# HotPotato.net
KiCad netlist of a schematic drawn in EAGLE
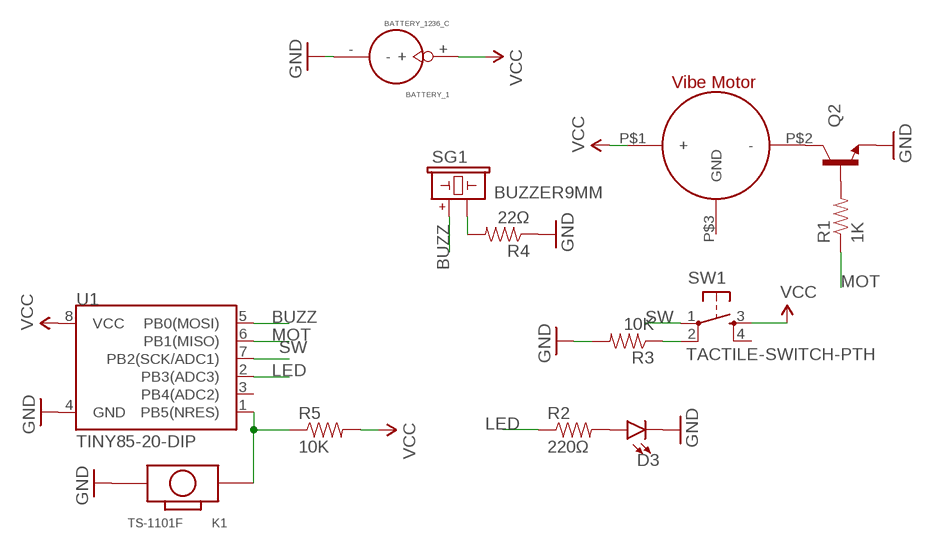
[diagram p0: schematic, sheet 1]

(export (version "E")
  (design (tool "Eeschema 10.0.6"))
  (components
    (comp (ref "BATTERY_1")
      (value "BATTERY_1236_C")
      (footprint "eagle-import:BATTERY_1236_C")
      (libsource (lib "eagle-import") (part "BATTERY_1236_C"))
    )
    (comp (ref "D3")
      (value "LED5MM-KIT")
      (footprint "eagle-import:LED_5MM-KIT")
      (libsource (lib "eagle-import") (part "LED5MM-KIT"))
    )
    (comp (ref "K1")
      (value "TS-1101F")
      (footprint "eagle-import:SW2-3.4X6.0X3.55MM-90D")
      (libsource (lib "eagle-import") (part "DIP-BUTTON-FRONT-WHITE(2P-3.4X6MM)"))
    )
    (comp (ref "M1")
      (value "SANYO_NRS-2574SMT")
      (footprint "eagle-import:SMT")
      (libsource (lib "eagle-import") (part "SANYO_NRS-2574SMT"))
    )
    (comp (ref "Q2")
      (value "TRANSISTOR_NPNBC547")
      (footprint "eagle-import:TO-92-AMMO")
      (libsource (lib "eagle-import") (part "TRANSISTOR_NPNBC547"))
    )
    (comp (ref "R1")
      (value "1K")
      (footprint "eagle-import:1206")
      (libsource (lib "eagle-import") (part "RESISTOR1206"))
    )
    (comp (ref "R2")
      (value "220Ω")
      (footprint "eagle-import:1206")
      (libsource (lib "eagle-import") (part "RESISTOR1206"))
    )
    (comp (ref "R3")
      (value "10K")
      (footprint "eagle-import:1206")
      (libsource (lib "eagle-import") (part "RESISTOR1206"))
    )
    (comp (ref "R4")
      (value "22Ω")
      (footprint "eagle-import:1206")
      (libsource (lib "eagle-import") (part "RESISTOR1206"))
    )
    (comp (ref "R5")
      (value "10K")
      (footprint "eagle-import:1206")
      (libsource (lib "eagle-import") (part "RESISTOR1206"))
    )
    (comp (ref "SG1")
      (value "BUZZER9MM")
      (footprint "eagle-import:BUZZER-9MM-PTH_NEW")
      (libsource (lib "eagle-import") (part "BUZZER9MM"))
    )
    (comp (ref "SW1")
      (value "TACTILE-SWITCH-PTH")
      (footprint "eagle-import:TAC-SWITCH-PTH")
      (libsource (lib "eagle-import") (part "TACTILE-SWITCH-PTH"))
    )
    (comp (ref "U1")
      (value "TINY85-20-DIP")
      (footprint "eagle-import:DIP08")
      (libsource (lib "eagle-import") (part "ATTINY45TINY85-20-DIP"))
    )
  )
  (nets
    (net (code "1") (name "/BUZZ") (class "Default")
      (node (ref "SG1") (pin "P$1") (pinfunction "1_P$1") (pintype "passive"))
      (node (ref "U1") (pin "5") (pinfunction "PB0(MOSI)_5") (pintype "bidirectional"))
    )
    (net (code "2") (name "/LED") (class "Default")
      (node (ref "R2") (pin "1") (pinfunction "1_1") (pintype "passive"))
      (node (ref "U1") (pin "2") (pinfunction "PB3(ADC3)_2") (pintype "bidirectional"))
    )
    (net (code "3") (name "/MOT") (class "Default")
      (node (ref "R1") (pin "1") (pinfunction "1_1") (pintype "passive"))
      (node (ref "U1") (pin "6") (pinfunction "PB1(MISO)_6") (pintype "bidirectional"))
    )
    (net (code "4") (name "/SW") (class "Default")
      (node (ref "SW1") (pin "1") (pinfunction "1_1") (pintype "passive"))
      (node (ref "U1") (pin "7") (pinfunction "PB2(SCK/ADC1)_7") (pintype "bidirectional"))
    )
    (net (code "5") (name "GND") (class "Default")
      (node (ref "BATTERY_1") (pin "-") (pinfunction "-_-") (pintype "bidirectional"))
      (node (ref "D3") (pin "K") (pinfunction "C_K") (pintype "passive"))
      (node (ref "K1") (pin "P$2") (pinfunction "2_P$2") (pintype "bidirectional"))
      (node (ref "Q2") (pin "3") (pinfunction "E_3") (pintype "passive"))
      (node (ref "R3") (pin "2") (pinfunction "2_2") (pintype "passive"))
      (node (ref "R4") (pin "1") (pinfunction "1_1") (pintype "passive"))
      (node (ref "U1") (pin "4") (pinfunction "GND_4") (pintype "bidirectional"))
    )
    (net (code "6") (name "Net-(D3-PadA)") (class "Default")
      (node (ref "D3") (pin "A") (pinfunction "A_A") (pintype "passive"))
      (node (ref "R2") (pin "2") (pinfunction "2_2") (pintype "passive"))
    )
    (net (code "7") (name "Net-(K1-1)") (class "Default")
      (node (ref "K1") (pin "P$1") (pinfunction "1_P$1") (pintype "bidirectional"))
      (node (ref "R5") (pin "1") (pinfunction "1_1") (pintype "passive"))
      (node (ref "U1") (pin "1") (pinfunction "PB5(NRES)_1") (pintype "bidirectional"))
    )
    (net (code "8") (name "Net-(M1--)") (class "Default")
      (node (ref "M1") (pin "P$2") (pinfunction "-_P$2") (pintype "output"))
      (node (ref "Q2") (pin "1") (pinfunction "C_1") (pintype "passive"))
    )
    (net (code "9") (name "Net-(Q2-B)") (class "Default")
      (node (ref "Q2") (pin "2") (pinfunction "B_2") (pintype "passive"))
      (node (ref "R1") (pin "2") (pinfunction "2_2") (pintype "passive"))
    )
    (net (code "10") (name "Net-(R3-Pad1)") (class "Default")
      (node (ref "R3") (pin "1") (pinfunction "1_1") (pintype "passive"))
      (node (ref "SW1") (pin "2") (pinfunction "2_2") (pintype "passive"))
    )
    (net (code "11") (name "Net-(SG1-2)") (class "Default")
      (node (ref "R4") (pin "2") (pinfunction "2_2") (pintype "passive"))
      (node (ref "SG1") (pin "P$2") (pinfunction "2_P$2") (pintype "passive"))
    )
    (net (code "12") (name "VCC") (class "Default")
      (node (ref "BATTERY_1") (pin "+") (pinfunction "+_+") (pintype "bidirectional"))
      (node (ref "M1") (pin "P$1") (pinfunction "+_P$1") (pintype "input"))
      (node (ref "R5") (pin "2") (pinfunction "2_2") (pintype "passive"))
      (node (ref "SW1") (pin "3") (pinfunction "3_3") (pintype "passive"))
      (node (ref "U1") (pin "8") (pinfunction "VCC_8") (pintype "bidirectional"))
    )
    (net (code "13") (name "unconnected-(M1-GND-PadP$3)") (class "Default")
      (node (ref "M1") (pin "P$3") (pinfunction "GND_P$3") (pintype "bidirectional"))
    )
    (net (code "14") (name "unconnected-(SW1-Pad4)") (class "Default")
      (node (ref "SW1") (pin "4") (pinfunction "4_4") (pintype "passive"))
    )
    (net (code "15") (name "unconnected-(U1-PB4(ADC2)-Pad3)") (class "Default")
      (node (ref "U1") (pin "3") (pinfunction "PB4(ADC2)_3") (pintype "bidirectional"))
    )
  )
)
